# tinyRF.net
KiCad netlist of a schematic drawn in EAGLE
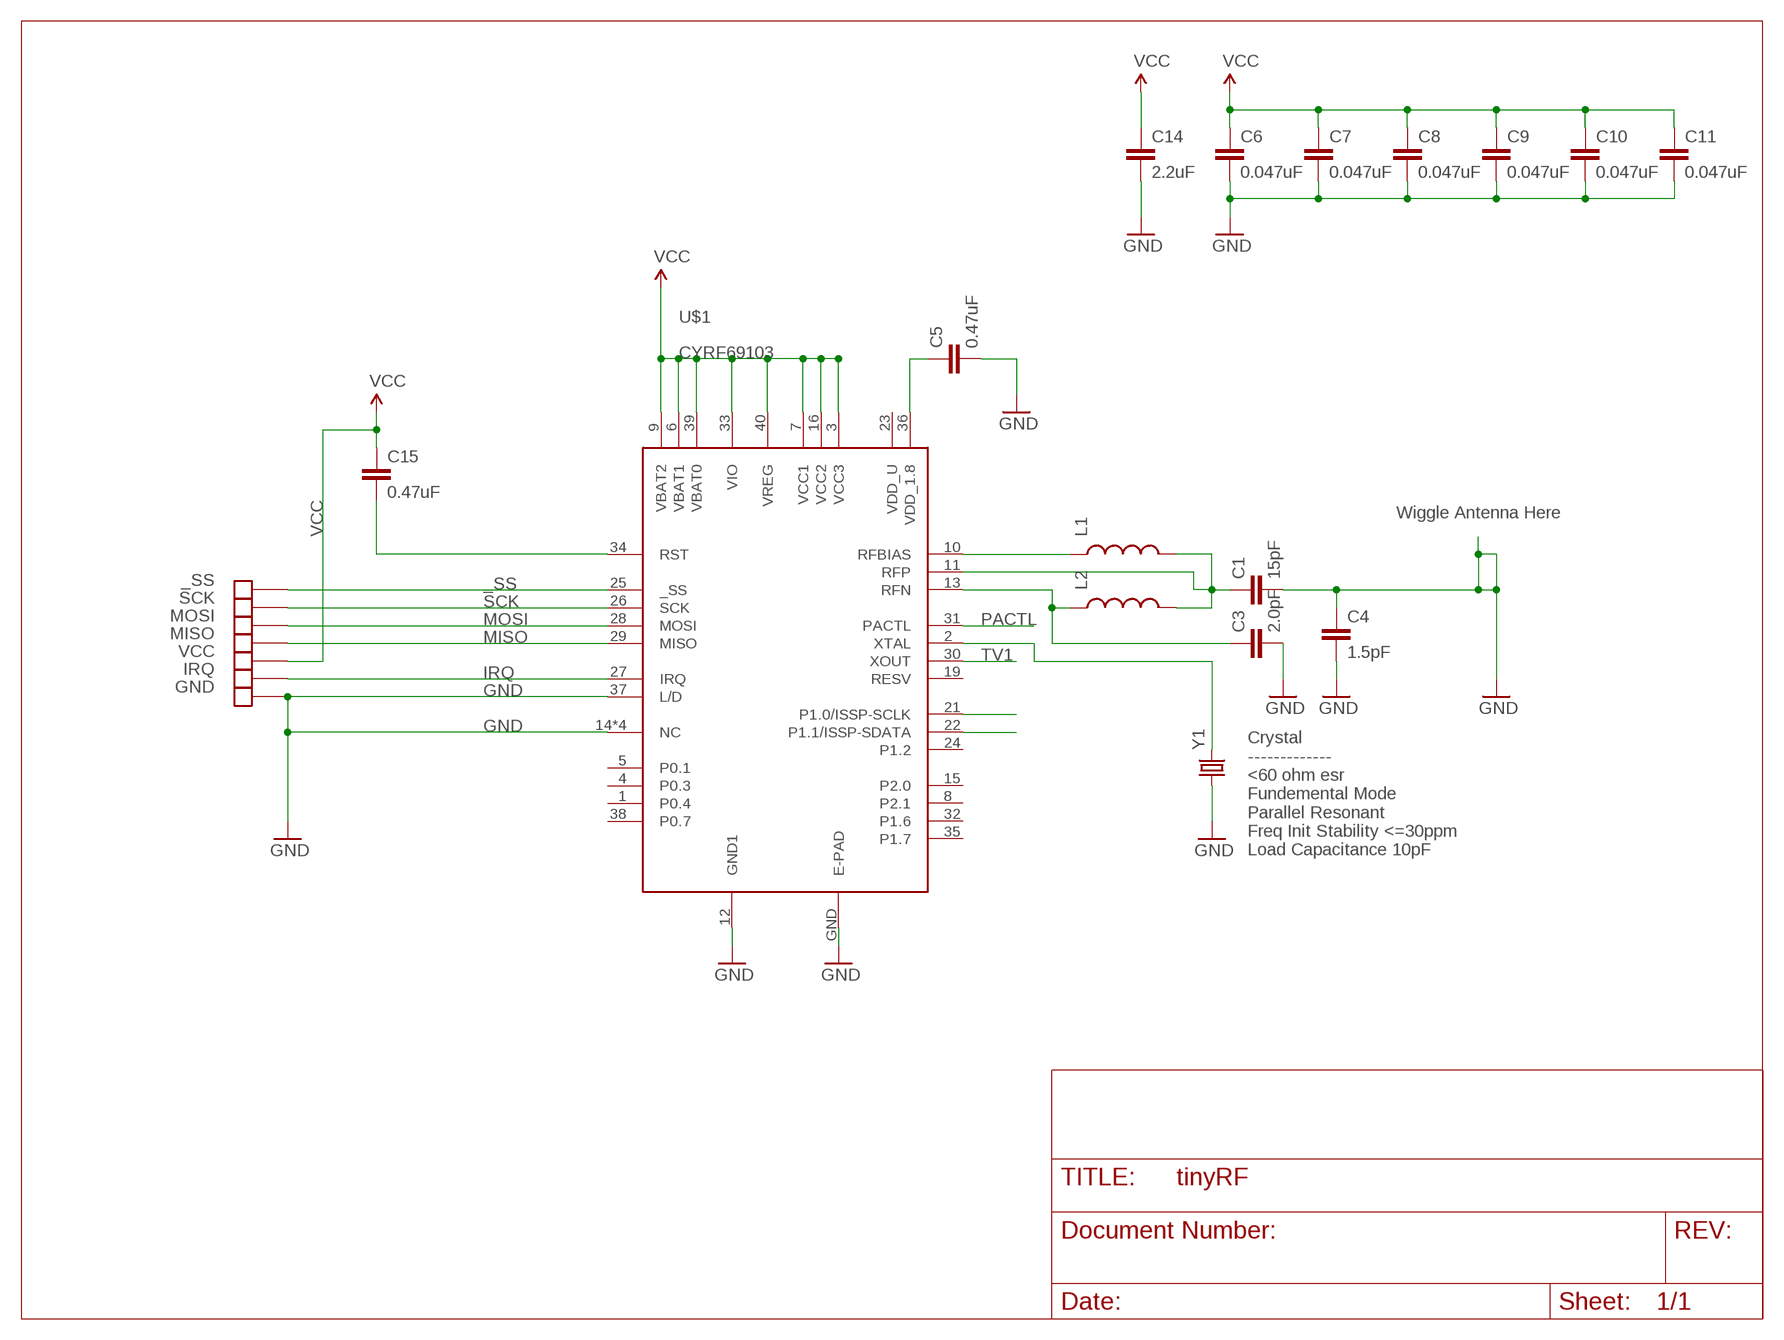
[diagram p0: schematic, sheet 1]

(export (version "E")
  (design (tool "Eeschema 10.0.6"))
  (components
    (comp (ref "C1")
      (value "15pF")
      (footprint "eagle-import:0402-CAP")
      (fields (field (name "PARTNO") "C0402C150J5GACTU"))
      (libsource (lib "eagle-import") (part "CAP0402-CAP"))
    )
    (comp (ref "C3")
      (value "2.0pF")
      (footprint "eagle-import:0402-CAP")
      (fields (field (name "PARTNO") "C0402C209C5GACTU"))
      (libsource (lib "eagle-import") (part "CAP0402-CAP"))
    )
    (comp (ref "C4")
      (value "1.5pF")
      (footprint "eagle-import:0402-CAP")
      (fields (field (name "PARTNO") "C0402C159B5GACTU"))
      (libsource (lib "eagle-import") (part "CAP0402-CAP"))
    )
    (comp (ref "C5")
      (value "0.47uF")
      (footprint "eagle-import:0402-CAP")
      (fields (field (name "PARTNO") "GRM155R60J474KE19D"))
      (libsource (lib "eagle-import") (part "CAP0402-CAP"))
    )
    (comp (ref "C6")
      (value "0.047uF")
      (footprint "eagle-import:0402-CAP")
      (fields (field (name "PARTNO") "0402YD473KAT2A"))
      (libsource (lib "eagle-import") (part "CAP0402-CAP"))
    )
    (comp (ref "C7")
      (value "0.047uF")
      (footprint "eagle-import:0402-CAP")
      (fields (field (name "PARTNO") "0402YD473KAT2A"))
      (libsource (lib "eagle-import") (part "CAP0402-CAP"))
    )
    (comp (ref "C8")
      (value "0.047uF")
      (footprint "eagle-import:0402-CAP")
      (fields (field (name "PARTNO") "0402YD473KAT2A"))
      (libsource (lib "eagle-import") (part "CAP0402-CAP"))
    )
    (comp (ref "C9")
      (value "0.047uF")
      (footprint "eagle-import:0402-CAP")
      (fields (field (name "PARTNO") "0402YD473KAT2A"))
      (libsource (lib "eagle-import") (part "CAP0402-CAP"))
    )
    (comp (ref "C10")
      (value "0.047uF")
      (footprint "eagle-import:0402-CAP")
      (fields (field (name "PARTNO") "0402YD473KAT2A"))
      (libsource (lib "eagle-import") (part "CAP0402-CAP"))
    )
    (comp (ref "C11")
      (value "0.047uF")
      (footprint "eagle-import:0402-CAP")
      (fields (field (name "PARTNO") "0402YD473KAT2A"))
      (libsource (lib "eagle-import") (part "CAP0402-CAP"))
    )
    (comp (ref "C14")
      (value "2.2uF")
      (footprint "eagle-import:0805")
      (fields (field (name "PARTNO") "GRM21BR71A225KA01L"))
      (libsource (lib "eagle-import") (part "CAP0805"))
    )
    (comp (ref "C15")
      (value "0.47uF")
      (footprint "eagle-import:0402-CAP")
      (fields (field (name "PARTNO") "GRM155R60J474KE19D"))
      (libsource (lib "eagle-import") (part "CAP0402-CAP"))
    )
    (comp (ref "GND")
      (value "SOLDER_PAD.05X.05")
      (footprint "eagle-import:SOLDER_PAD_.05X.05")
      (libsource (lib "eagle-import") (part "SOLDER_PAD.05X.05"))
    )
    (comp (ref "IRQ")
      (value "SOLDER_PAD.05X.05")
      (footprint "eagle-import:SOLDER_PAD_.05X.05")
      (libsource (lib "eagle-import") (part "SOLDER_PAD.05X.05"))
    )
    (comp (ref "L1")
      (value "INDUCTOR0603")
      (footprint "eagle-import:0603")
      (fields (field (name "PARTNO") "ELJ-RE22NGFA"))
      (libsource (lib "eagle-import") (part "INDUCTOR0603"))
    )
    (comp (ref "L2")
      (value "INDUCTOR0402")
      (footprint "eagle-import:C0402")
      (fields (field (name "PARTNO") "ELJ-RF1N8DFB"))
      (libsource (lib "eagle-import") (part "INDUCTOR0402"))
    )
    (comp (ref "MISO")
      (value "SOLDER_PAD.05X.05")
      (footprint "eagle-import:SOLDER_PAD_.05X.05")
      (libsource (lib "eagle-import") (part "SOLDER_PAD.05X.05"))
    )
    (comp (ref "MOSI")
      (value "SOLDER_PAD.05X.05")
      (footprint "eagle-import:SOLDER_PAD_.05X.05")
      (libsource (lib "eagle-import") (part "SOLDER_PAD.05X.05"))
    )
    (comp (ref "SCK")
      (value "SOLDER_PAD.05X.05")
      (footprint "eagle-import:SOLDER_PAD_.05X.05")
      (libsource (lib "eagle-import") (part "SOLDER_PAD.05X.05"))
    )
    (comp (ref "U$1")
      (value "CYRF69103")
      (footprint "eagle-import:QFN40")
      (libsource (lib "eagle-import") (part "CYRF69103"))
    )
    (comp (ref "VCC")
      (value "SOLDER_PAD.05X.05")
      (footprint "eagle-import:SOLDER_PAD_.05X.05")
      (libsource (lib "eagle-import") (part "SOLDER_PAD.05X.05"))
    )
    (comp (ref "Y1")
      (value "CRYSTAL5X3")
      (footprint "eagle-import:CRYSTAL-SMD-5X3")
      (fields (field (name "PARTNO") "7B-12.000MEEQ-T"))
      (libsource (lib "eagle-import") (part "CRYSTAL5X3"))
    )
    (comp (ref "_SS")
      (value "SOLDER_PAD.05X.05")
      (footprint "eagle-import:SOLDER_PAD_.05X.05")
      (libsource (lib "eagle-import") (part "SOLDER_PAD.05X.05"))
    )
  )
  (nets
    (net (code "1") (name "/IRQ") (class "Default")
      (node (ref "IRQ") (pin "P$1") (pinfunction "NET_P$1") (pintype "bidirectional"))
      (node (ref "U$1") (pin "27") (pinfunction "IRQ_27") (pintype "bidirectional"))
    )
    (net (code "2") (name "/MISO") (class "Default")
      (node (ref "MISO") (pin "P$1") (pinfunction "NET_P$1") (pintype "bidirectional"))
      (node (ref "U$1") (pin "29") (pinfunction "MISO_29") (pintype "bidirectional"))
    )
    (net (code "3") (name "/MOSI") (class "Default")
      (node (ref "MOSI") (pin "P$1") (pinfunction "NET_P$1") (pintype "bidirectional"))
      (node (ref "U$1") (pin "28") (pinfunction "MOSI_28") (pintype "bidirectional"))
    )
    (net (code "4") (name "/PACTL") (class "Default")
      (node (ref "U$1") (pin "31") (pinfunction "PACTL_31") (pintype "bidirectional"))
    )
    (net (code "5") (name "/SCK") (class "Default")
      (node (ref "SCK") (pin "P$1") (pinfunction "NET_P$1") (pintype "bidirectional"))
      (node (ref "U$1") (pin "26") (pinfunction "SCK_26") (pintype "bidirectional"))
    )
    (net (code "6") (name "/TV1") (class "Default")
      (node (ref "U$1") (pin "30") (pinfunction "XOUT_30") (pintype "bidirectional"))
    )
    (net (code "7") (name "/_SS") (class "Default")
      (node (ref "U$1") (pin "25") (pinfunction "_SS_25") (pintype "bidirectional"))
      (node (ref "_SS") (pin "P$1") (pinfunction "NET_P$1") (pintype "bidirectional"))
    )
    (net (code "8") (name "GND") (class "Default")
      (node (ref "C1") (pin "2") (pinfunction "2_2") (pintype "passive"))
      (node (ref "C10") (pin "2") (pinfunction "2_2") (pintype "passive"))
      (node (ref "C11") (pin "2") (pinfunction "2_2") (pintype "passive"))
      (node (ref "C14") (pin "2") (pinfunction "2_2") (pintype "passive"))
      (node (ref "C3") (pin "2") (pinfunction "2_2") (pintype "passive"))
      (node (ref "C4") (pin "1") (pinfunction "1_1") (pintype "passive"))
      (node (ref "C4") (pin "2") (pinfunction "2_2") (pintype "passive"))
      (node (ref "C5") (pin "2") (pinfunction "2_2") (pintype "passive"))
      (node (ref "C6") (pin "2") (pinfunction "2_2") (pintype "passive"))
      (node (ref "C7") (pin "2") (pinfunction "2_2") (pintype "passive"))
      (node (ref "C8") (pin "2") (pinfunction "2_2") (pintype "passive"))
      (node (ref "C9") (pin "2") (pinfunction "2_2") (pintype "passive"))
      (node (ref "GND") (pin "P$1") (pinfunction "NET_P$1") (pintype "bidirectional"))
      (node (ref "U$1") (pin "12") (pinfunction "GND1_12") (pintype "bidirectional"))
      (node (ref "U$1") (pin "14") (pinfunction "NC_14") (pintype "bidirectional"))
      (node (ref "U$1") (pin "17") (pinfunction "NC_17") (pintype "bidirectional"))
      (node (ref "U$1") (pin "18") (pinfunction "NC_18") (pintype "bidirectional"))
      (node (ref "U$1") (pin "20") (pinfunction "NC_20") (pintype "bidirectional"))
      (node (ref "U$1") (pin "37") (pinfunction "L/D_37") (pintype "bidirectional"))
      (node (ref "U$1") (pin "GND") (pinfunction "E-PAD_GND") (pintype "bidirectional"))
      (node (ref "Y1") (pin "1") (pinfunction "1_1") (pintype "passive"))
    )
    (net (code "9") (name "Net-(U$1-RFBIAS)") (class "Default")
      (node (ref "L1") (pin "1") (pinfunction "1_1") (pintype "passive"))
      (node (ref "U$1") (pin "10") (pinfunction "RFBIAS_10") (pintype "bidirectional"))
    )
    (net (code "10") (name "Net-(U$1-RFN)") (class "Default")
      (node (ref "C3") (pin "1") (pinfunction "1_1") (pintype "passive"))
      (node (ref "L2") (pin "1") (pinfunction "1_1") (pintype "passive"))
      (node (ref "U$1") (pin "13") (pinfunction "RFN_13") (pintype "bidirectional"))
    )
    (net (code "11") (name "Net-(U$1-RFP)") (class "Default")
      (node (ref "C1") (pin "1") (pinfunction "1_1") (pintype "passive"))
      (node (ref "L1") (pin "2") (pinfunction "2_2") (pintype "passive"))
      (node (ref "L2") (pin "2") (pinfunction "2_2") (pintype "passive"))
      (node (ref "U$1") (pin "11") (pinfunction "RFP_11") (pintype "bidirectional"))
    )
    (net (code "12") (name "Net-(U$1-RST)") (class "Default")
      (node (ref "C15") (pin "2") (pinfunction "2_2") (pintype "passive"))
      (node (ref "U$1") (pin "34") (pinfunction "RST_34") (pintype "bidirectional"))
    )
    (net (code "13") (name "Net-(U$1-VDD_1.8)") (class "Default")
      (node (ref "C5") (pin "1") (pinfunction "1_1") (pintype "passive"))
      (node (ref "U$1") (pin "36") (pinfunction "VDD_1.8_36") (pintype "bidirectional"))
    )
    (net (code "14") (name "Net-(U$1-XTAL)") (class "Default")
      (node (ref "U$1") (pin "2") (pinfunction "XTAL_2") (pintype "bidirectional"))
      (node (ref "Y1") (pin "3") (pinfunction "2_3") (pintype "passive"))
    )
    (net (code "15") (name "VCC") (class "Default")
      (node (ref "C10") (pin "1") (pinfunction "1_1") (pintype "passive"))
      (node (ref "C11") (pin "1") (pinfunction "1_1") (pintype "passive"))
      (node (ref "C14") (pin "1") (pinfunction "1_1") (pintype "passive"))
      (node (ref "C15") (pin "1") (pinfunction "1_1") (pintype "passive"))
      (node (ref "C6") (pin "1") (pinfunction "1_1") (pintype "passive"))
      (node (ref "C7") (pin "1") (pinfunction "1_1") (pintype "passive"))
      (node (ref "C8") (pin "1") (pinfunction "1_1") (pintype "passive"))
      (node (ref "C9") (pin "1") (pinfunction "1_1") (pintype "passive"))
      (node (ref "U$1") (pin "16") (pinfunction "VCC2_16") (pintype "bidirectional"))
      (node (ref "U$1") (pin "3") (pinfunction "VCC3_3") (pintype "bidirectional"))
      (node (ref "U$1") (pin "33") (pinfunction "VIO_33") (pintype "bidirectional"))
      (node (ref "U$1") (pin "39") (pinfunction "VBAT0_39") (pintype "bidirectional"))
      (node (ref "U$1") (pin "40") (pinfunction "VREG_40") (pintype "bidirectional"))
      (node (ref "U$1") (pin "6") (pinfunction "VBAT1_6") (pintype "bidirectional"))
      (node (ref "U$1") (pin "7") (pinfunction "VCC1_7") (pintype "bidirectional"))
      (node (ref "U$1") (pin "9") (pinfunction "VBAT2_9") (pintype "bidirectional"))
      (node (ref "VCC") (pin "P$1") (pinfunction "NET_P$1") (pintype "bidirectional"))
    )
    (net (code "16") (name "unconnected-(U$1-P0.1-Pad5)") (class "Default")
      (node (ref "U$1") (pin "5") (pinfunction "P0.1_5") (pintype "bidirectional"))
    )
    (net (code "17") (name "unconnected-(U$1-P0.3-Pad4)") (class "Default")
      (node (ref "U$1") (pin "4") (pinfunction "P0.3_4") (pintype "bidirectional"))
    )
    (net (code "18") (name "unconnected-(U$1-P0.4-Pad1)") (class "Default")
      (node (ref "U$1") (pin "1") (pinfunction "P0.4_1") (pintype "bidirectional"))
    )
    (net (code "19") (name "unconnected-(U$1-P0.7-Pad38)") (class "Default")
      (node (ref "U$1") (pin "38") (pinfunction "P0.7_38") (pintype "bidirectional"))
    )
    (net (code "20") (name "unconnected-(U$1-P1.0{slash}ISSP-SCLK-Pad21)") (class "Default")
      (node (ref "U$1") (pin "21") (pinfunction "P1.0/ISSP-SCLK_21") (pintype "bidirectional"))
    )
    (net (code "21") (name "unconnected-(U$1-P1.1{slash}ISSP-SDATA-Pad22)") (class "Default")
      (node (ref "U$1") (pin "22") (pinfunction "P1.1/ISSP-SDATA_22") (pintype "bidirectional"))
    )
    (net (code "22") (name "unconnected-(U$1-P1.2-Pad24)") (class "Default")
      (node (ref "U$1") (pin "24") (pinfunction "P1.2_24") (pintype "bidirectional"))
    )
    (net (code "23") (name "unconnected-(U$1-P1.6-Pad32)") (class "Default")
      (node (ref "U$1") (pin "32") (pinfunction "P1.6_32") (pintype "bidirectional"))
    )
    (net (code "24") (name "unconnected-(U$1-P1.7-Pad35)") (class "Default")
      (node (ref "U$1") (pin "35") (pinfunction "P1.7_35") (pintype "bidirectional"))
    )
    (net (code "25") (name "unconnected-(U$1-P2.0-Pad15)") (class "Default")
      (node (ref "U$1") (pin "15") (pinfunction "P2.0_15") (pintype "bidirectional"))
    )
    (net (code "26") (name "unconnected-(U$1-P2.1-Pad8)") (class "Default")
      (node (ref "U$1") (pin "8") (pinfunction "P2.1_8") (pintype "bidirectional"))
    )
    (net (code "27") (name "unconnected-(U$1-RESV-Pad19)") (class "Default")
      (node (ref "U$1") (pin "19") (pinfunction "RESV_19") (pintype "bidirectional"))
    )
    (net (code "28") (name "unconnected-(U$1-VDD_U-Pad23)") (class "Default")
      (node (ref "U$1") (pin "23") (pinfunction "VDD_U_23") (pintype "bidirectional"))
    )
  )
)
